# RackEth.net
KiCad netlist of a schematic drawn in EasyEDA Pro
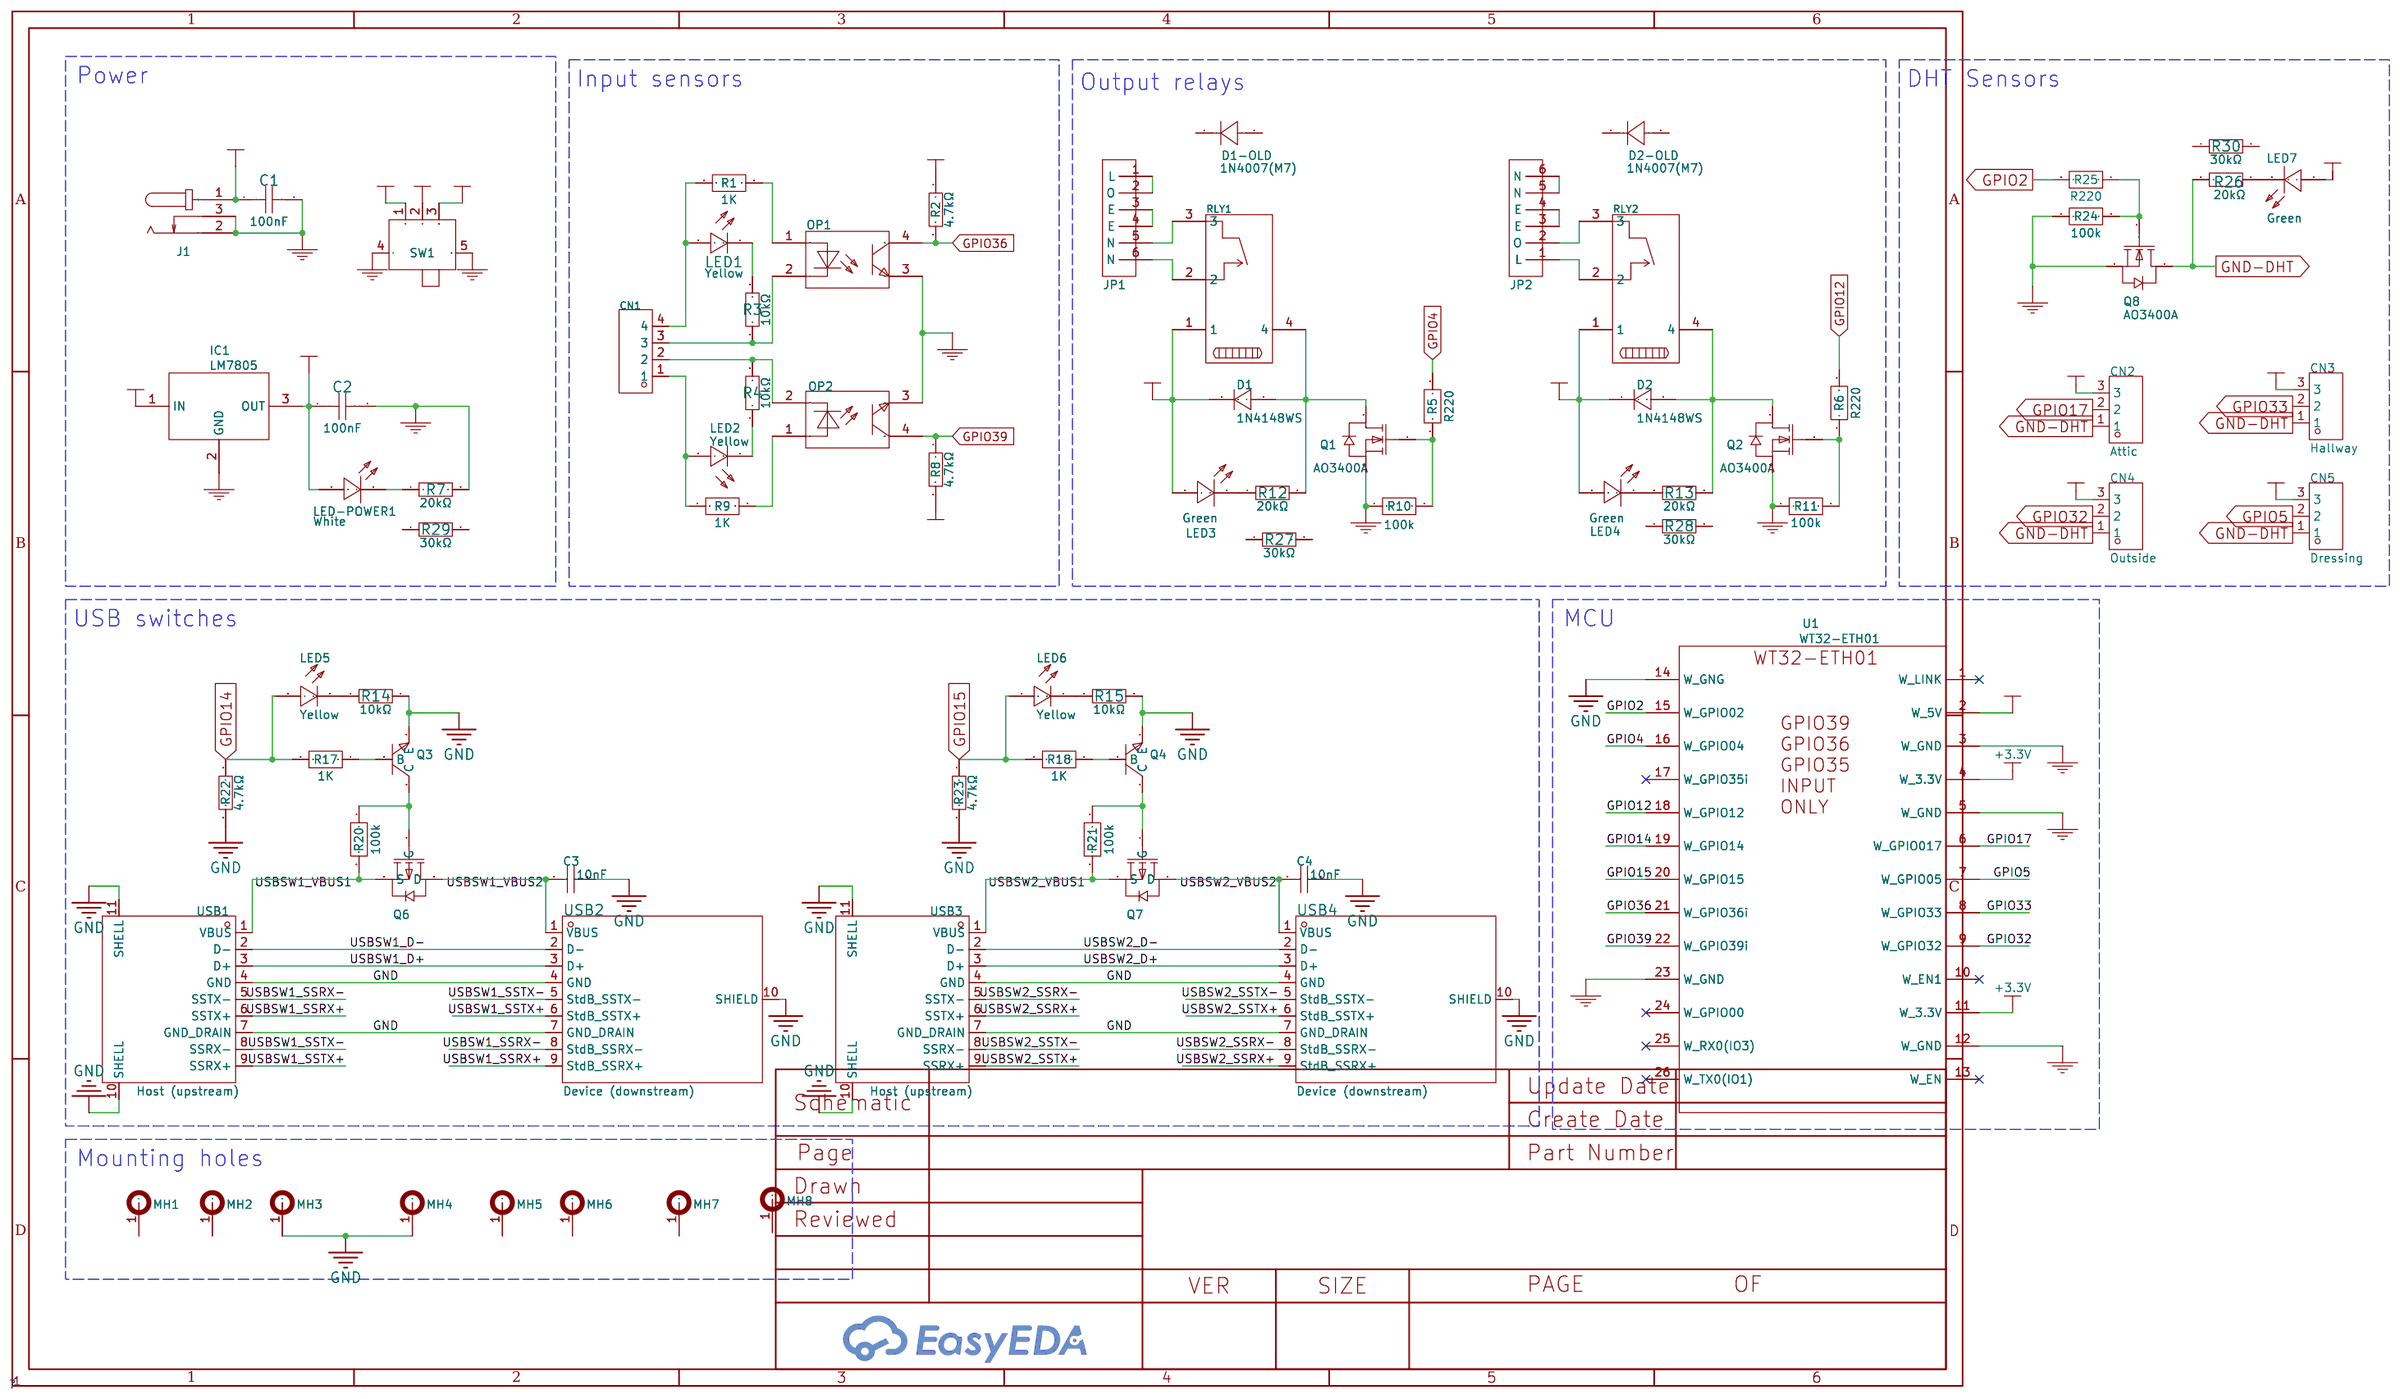
[diagram p0: schematic sheet]

(export (version "E")
  (design (tool "Eeschema 10.0.6"))
  (components
    (comp (ref "C1")
      (value "100nF")
      (footprint "easyedapro:C0603")
      (fields
        (field (name "Manufacturer Part") "CC0603KRX7R9BB104")
        (field (name "Manufacturer") "YAGEO(国巨)")
      )
      (libsource (lib "easyedapro") (part "CC0603KRX7R9BB104"))
    )
    (comp (ref "C2")
      (value "100nF")
      (footprint "easyedapro:C0603")
      (fields
        (field (name "Manufacturer Part") "CC0603KRX7R9BB104")
        (field (name "Manufacturer") "YAGEO(国巨)")
      )
      (libsource (lib "easyedapro") (part "CC0603KRX7R9BB104"))
    )
    (comp (ref "C3")
      (value "10nF")
      (footprint "easyedapro:C0402")
      (fields
        (field (name "Manufacturer Part") "CL05B103KB5NNNC")
        (field (name "Manufacturer") "SAMSUNG(三星)")
      )
      (libsource (lib "easyedapro") (part "CL05B103KB5NNNC"))
    )
    (comp (ref "C4")
      (value "10nF")
      (footprint "easyedapro:C0402")
      (fields
        (field (name "Manufacturer Part") "CL05B103KB5NNNC")
        (field (name "Manufacturer") "SAMSUNG(三星)")
      )
      (libsource (lib "easyedapro") (part "CL05B103KB5NNNC"))
    )
    (comp (ref "CN1")
      (value "WJ127-5.0-4P")
      (footprint "easyedapro:CONN-TH_4P-P5.00_WJ127-5.0-4P")
      (fields (field (name "Manufacturer") "KANGNEX(康奈克斯电气)"))
      (libsource (lib "easyedapro") (part "WJ127-5.0-4P"))
    )
    (comp (ref "CN2")
      (value "Attic")
      (footprint "easyedapro:CONN-TH_3P-P2.50_HCTL_XH-3A-L")
      (fields (field (name "Manufacturer Part") "XH2.54-3A"))
      (libsource (lib "easyedapro") (part "XH2.54-3A"))
    )
    (comp (ref "CN3")
      (value "Hallway")
      (footprint "easyedapro:CONN-TH_3P-P2.50_HCTL_XH-3A-L")
      (fields (field (name "Manufacturer Part") "XH2.54-3A"))
      (libsource (lib "easyedapro") (part "XH2.54-3A"))
    )
    (comp (ref "CN4")
      (value "Outside")
      (footprint "easyedapro:CONN-TH_3P-P2.50_HCTL_XH-3A-L")
      (fields (field (name "Manufacturer Part") "XH2.54-3A"))
      (libsource (lib "easyedapro") (part "XH2.54-3A"))
    )
    (comp (ref "CN5")
      (value "Dressing")
      (footprint "easyedapro:CONN-TH_3P-P2.50_HCTL_XH-3A-L")
      (fields (field (name "Manufacturer Part") "XH2.54-3A"))
      (libsource (lib "easyedapro") (part "XH2.54-3A"))
    )
    (comp (ref "D1")
      (value "1N4148WS")
      (footprint "easyedapro:SOD-323_L1.8-W1.3-LS2.5-RD")
      (fields (field (name "Manufacturer") "CJ(江苏长电/长晶)"))
      (libsource (lib "easyedapro") (part "1N4148WS T4"))
    )
    (comp (ref "D1-OLD")
      (value "1N4007(M7)")
      (footprint "easyedapro:SMA_L4.3-W2.7-LS5.1-RD")
      (fields (field (name "Manufacturer") "UMW(友台半导体)"))
      (libsource (lib "easyedapro") (part "1N4007(M7)"))
    )
    (comp (ref "D2")
      (value "1N4148WS")
      (footprint "easyedapro:SOD-323_L1.8-W1.3-LS2.5-RD")
      (fields (field (name "Manufacturer") "CJ(江苏长电/长晶)"))
      (libsource (lib "easyedapro") (part "1N4148WS T4"))
    )
    (comp (ref "D2-OLD")
      (value "1N4007(M7)")
      (footprint "easyedapro:SMA_L4.3-W2.7-LS5.1-RD")
      (fields (field (name "Manufacturer") "UMW(友台半导体)"))
      (libsource (lib "easyedapro") (part "1N4007(M7)"))
    )
    (comp (ref "IC1")
      (value "LM7805")
      (footprint "easyedapro:LM7805")
      (libsource (lib "easyedapro") (part "LM7805"))
    )
    (comp (ref "J1")
      (value "DC005-2.1x5.5mm")
      (footprint "easyedapro:DC-IN-TH_POWER-JACK")
      (fields (field (name "Manufacturer Part") "POWER-JACK") (field (name "Manufacturer") "索峰"))
      (libsource (lib "easyedapro") (part "DC005-2.1x5.5mm"))
    )
    (comp (ref "JP1") (value "JP1") (libsource (lib "easyedapro") (part "Terminal?")))
    (comp (ref "JP2") (value "JP2") (libsource (lib "easyedapro") (part "Terminal?")))
    (comp (ref "LED-POWER1")
      (value "White")
      (footprint "easyedapro:LED0603-R-RD_WHITE")
      (fields (field (name "Manufacturer Part") "KT-0603W") (field (name "Manufacturer") "KENTO"))
      (libsource (lib "easyedapro") (part "0603White light_C2290"))
    )
    (comp (ref "LED1")
      (value "Yellow")
      (footprint "easyedapro:LED0603-RD-YELLOW")
      (fields
        (field (name "Manufacturer Part") "19-213/Y2C-CQ2R2L/3T(CY)")
        (field (name "Manufacturer") "EVERLIGHT(亿光)")
      )
      (libsource (lib "easyedapro") (part "19-213/Y2C-CQ2R2L/3T(CY)"))
    )
    (comp (ref "LED2")
      (value "Yellow")
      (footprint "easyedapro:LED0603-RD-YELLOW")
      (fields
        (field (name "Manufacturer Part") "19-213/Y2C-CQ2R2L/3T(CY)")
        (field (name "Manufacturer") "EVERLIGHT(亿光)")
      )
      (libsource (lib "easyedapro") (part "19-213/Y2C-CQ2R2L/3T(CY)"))
    )
    (comp (ref "LED3")
      (value "Green")
      (footprint "easyedapro:LED0805-RD_GREEN")
      (fields (field (name "Manufacturer Part") "0805G (Green)") (field (name "Manufacturer") "KENTO"))
      (libsource (lib "easyedapro") (part "0805G (Green)"))
    )
    (comp (ref "LED4")
      (value "Green")
      (footprint "easyedapro:LED0805-RD_GREEN")
      (fields (field (name "Manufacturer Part") "0805G (Green)") (field (name "Manufacturer") "KENTO"))
      (libsource (lib "easyedapro") (part "0805G (Green)"))
    )
    (comp (ref "LED5")
      (value "Yellow")
      (footprint "easyedapro:LED0603-RD-YELLOW")
      (fields
        (field (name "Manufacturer Part") "19-213/Y2C-CQ2R2L/3T(CY)")
        (field (name "Manufacturer") "EVERLIGHT(亿光)")
      )
      (libsource (lib "easyedapro") (part "19-213/Y2C-CQ2R2L/3T(CY)"))
    )
    (comp (ref "LED6")
      (value "Yellow")
      (footprint "easyedapro:LED0603-RD-YELLOW")
      (fields
        (field (name "Manufacturer Part") "19-213/Y2C-CQ2R2L/3T(CY)")
        (field (name "Manufacturer") "EVERLIGHT(亿光)")
      )
      (libsource (lib "easyedapro") (part "19-213/Y2C-CQ2R2L/3T(CY)"))
    )
    (comp (ref "LED7")
      (value "Green")
      (footprint "easyedapro:LED0805-RD_GREEN")
      (fields (field (name "Manufacturer Part") "0805G (Green)") (field (name "Manufacturer") "KENTO"))
      (libsource (lib "easyedapro") (part "0805G (Green)"))
    )
    (comp (ref "MH1")
      (value "~")
      (footprint "easyedapro:MH_7.5x4mm")
      (libsource (lib "easyedapro") (part "MH_7.5x4mm"))
    )
    (comp (ref "MH2")
      (value "~")
      (footprint "easyedapro:MH_7.5x4mm")
      (libsource (lib "easyedapro") (part "MH_7.5x4mm"))
    )
    (comp (ref "MH3")
      (value "~")
      (footprint "easyedapro:MH_7.5x4mm")
      (libsource (lib "easyedapro") (part "MH_7.5x4mm"))
    )
    (comp (ref "MH4")
      (value "~")
      (footprint "easyedapro:MH_7.5x4mm")
      (libsource (lib "easyedapro") (part "MH_7.5x4mm"))
    )
    (comp (ref "MH5")
      (value "~")
      (footprint "easyedapro:MH_6x3.2mm")
      (libsource (lib "easyedapro") (part "MH_6x3.2mm"))
    )
    (comp (ref "MH6")
      (value "~")
      (footprint "easyedapro:MH_6x3.2mm")
      (libsource (lib "easyedapro") (part "MH_6x3.2mm"))
    )
    (comp (ref "MH7")
      (value "~")
      (footprint "easyedapro:MH_6x3.2mm")
      (libsource (lib "easyedapro") (part "MH_6x3.2mm"))
    )
    (comp (ref "MH8")
      (value "~")
      (footprint "easyedapro:MH_6x3.2mm")
      (libsource (lib "easyedapro") (part "MH_6x3.2mm"))
    )
    (comp (ref "OP1")
      (value "EL817S1(C)(TU)-F")
      (footprint "easyedapro:OPTO-SMD-4_L4.6-W6.5-P2.54-LS10.3-TL")
      (fields (field (name "Manufacturer") "EVERLIGHT(亿光)"))
      (libsource (lib "easyedapro") (part "EL817S1(C)(TU)-F"))
    )
    (comp (ref "OP2")
      (value "EL817S1(C)(TU)-F")
      (footprint "easyedapro:OPTO-SMD-4_L4.6-W6.5-P2.54-LS10.3-TL")
      (fields (field (name "Manufacturer") "EVERLIGHT(亿光)"))
      (libsource (lib "easyedapro") (part "EL817S1(C)(TU)-F"))
    )
    (comp (ref "Q1")
      (value "AO3400A")
      (footprint "easyedapro:SOT-23-3_L2.9-W1.6-P1.90-LS2.8-BR")
      (fields (field (name "Manufacturer") "AOS"))
      (libsource (lib "easyedapro") (part "AO3400A"))
    )
    (comp (ref "Q2")
      (value "AO3400A")
      (footprint "easyedapro:SOT-23-3_L2.9-W1.6-P1.90-LS2.8-BR")
      (fields (field (name "Manufacturer") "AOS"))
      (libsource (lib "easyedapro") (part "AO3400A"))
    )
    (comp (ref "Q3")
      (value "MMBT3904(RANGE:100-300)")
      (footprint "easyedapro:SOT-23-3_L2.9-W1.3-P1.90-LS2.4-BR")
      (fields (field (name "Manufacturer") "CJ(江苏长电/长晶)"))
      (libsource (lib "easyedapro") (part "MMBT3904"))
    )
    (comp (ref "Q4")
      (value "MMBT3904(RANGE:100-300)")
      (footprint "easyedapro:SOT-23-3_L2.9-W1.3-P1.90-LS2.4-BR")
      (fields (field (name "Manufacturer") "CJ(江苏长电/长晶)"))
      (libsource (lib "easyedapro") (part "MMBT3904"))
    )
    (comp (ref "Q6")
      (value "AO3401A")
      (footprint "easyedapro:SOT-23_L2.9-W1.3-P1.90-LS2.4-BR")
      (fields (field (name "Manufacturer") "AOS"))
      (libsource (lib "easyedapro") (part "AO3401A"))
    )
    (comp (ref "Q7")
      (value "AO3401A")
      (footprint "easyedapro:SOT-23_L2.9-W1.3-P1.90-LS2.4-BR")
      (fields (field (name "Manufacturer") "AOS"))
      (libsource (lib "easyedapro") (part "AO3401A"))
    )
    (comp (ref "Q8")
      (value "AO3400A")
      (footprint "easyedapro:SOT-23-3_L2.9-W1.6-P1.90-LS2.8-BR")
      (fields (field (name "Manufacturer") "AOS"))
      (libsource (lib "easyedapro") (part "AO3400A"))
    )
    (comp (ref "R1")
      (value "1K")
      (footprint "easyedapro:R0603")
      (fields
        (field (name "Manufacturer Part") "0603WAF1001T5E")
        (field (name "Manufacturer") "UNI-ROYAL(厚声)")
      )
      (libsource (lib "easyedapro") (part "1K"))
    )
    (comp (ref "R2")
      (value "4.7kΩ")
      (footprint "easyedapro:R0603")
      (fields
        (field (name "Manufacturer Part") "0603WAF4701T5E")
        (field (name "Manufacturer") "UNI-ROYAL(厚声)")
      )
      (libsource (lib "easyedapro") (part "0603WAF4701T5E"))
    )
    (comp (ref "R3")
      (value "10kΩ")
      (footprint "easyedapro:R0603")
      (fields
        (field (name "Manufacturer Part") "0603WAF1002T5E")
        (field (name "Manufacturer") "UNI-ROYAL(厚声)")
      )
      (libsource (lib "easyedapro") (part "0603WAF1002T5E"))
    )
    (comp (ref "R4")
      (value "10kΩ")
      (footprint "easyedapro:R0603")
      (fields
        (field (name "Manufacturer Part") "0603WAF1002T5E")
        (field (name "Manufacturer") "UNI-ROYAL(厚声)")
      )
      (libsource (lib "easyedapro") (part "0603WAF1002T5E"))
    )
    (comp (ref "R5")
      (value "R220")
      (footprint "easyedapro:R0603")
      (fields
        (field (name "Manufacturer Part") "0603WAF2200T5E")
        (field (name "Manufacturer") "UNI-ROYAL(厚声)")
      )
      (libsource (lib "easyedapro") (part "R220"))
    )
    (comp (ref "R6")
      (value "R220")
      (footprint "easyedapro:R0603")
      (fields
        (field (name "Manufacturer Part") "0603WAF2200T5E")
        (field (name "Manufacturer") "UNI-ROYAL(厚声)")
      )
      (libsource (lib "easyedapro") (part "R220"))
    )
    (comp (ref "R7")
      (value "20kΩ")
      (footprint "easyedapro:R0603")
      (fields
        (field (name "Manufacturer Part") "0603WAF2002T5E")
        (field (name "Manufacturer") "UNI-ROYAL(厚声)")
      )
      (libsource (lib "easyedapro") (part "0603WAF2002T5E"))
    )
    (comp (ref "R8")
      (value "4.7kΩ")
      (footprint "easyedapro:R0603")
      (fields
        (field (name "Manufacturer Part") "0603WAF4701T5E")
        (field (name "Manufacturer") "UNI-ROYAL(厚声)")
      )
      (libsource (lib "easyedapro") (part "0603WAF4701T5E"))
    )
    (comp (ref "R9")
      (value "1K")
      (footprint "easyedapro:R0603")
      (fields
        (field (name "Manufacturer Part") "0603WAF1001T5E")
        (field (name "Manufacturer") "UNI-ROYAL(厚声)")
      )
      (libsource (lib "easyedapro") (part "1K"))
    )
    (comp (ref "R10")
      (value "100k")
      (footprint "easyedapro:R0603")
      (fields
        (field (name "Manufacturer Part") "0603WAF1003T5E")
        (field (name "Manufacturer") "UNI-ROYAL(厚声)")
      )
      (libsource (lib "easyedapro") (part "100k"))
    )
    (comp (ref "R11")
      (value "100k")
      (footprint "easyedapro:R0603")
      (fields
        (field (name "Manufacturer Part") "0603WAF1003T5E")
        (field (name "Manufacturer") "UNI-ROYAL(厚声)")
      )
      (libsource (lib "easyedapro") (part "100k"))
    )
    (comp (ref "R12")
      (value "20kΩ")
      (footprint "easyedapro:R0603")
      (fields
        (field (name "Manufacturer Part") "0603WAF2002T5E")
        (field (name "Manufacturer") "UNI-ROYAL(厚声)")
      )
      (libsource (lib "easyedapro") (part "0603WAF2002T5E"))
    )
    (comp (ref "R13")
      (value "20kΩ")
      (footprint "easyedapro:R0603")
      (fields
        (field (name "Manufacturer Part") "0603WAF2002T5E")
        (field (name "Manufacturer") "UNI-ROYAL(厚声)")
      )
      (libsource (lib "easyedapro") (part "0603WAF2002T5E"))
    )
    (comp (ref "R14")
      (value "10kΩ")
      (footprint "easyedapro:R0603")
      (fields
        (field (name "Manufacturer Part") "0603WAF1002T5E")
        (field (name "Manufacturer") "UNI-ROYAL(厚声)")
      )
      (libsource (lib "easyedapro") (part "0603WAF1002T5E"))
    )
    (comp (ref "R15")
      (value "10kΩ")
      (footprint "easyedapro:R0603")
      (fields
        (field (name "Manufacturer Part") "0603WAF1002T5E")
        (field (name "Manufacturer") "UNI-ROYAL(厚声)")
      )
      (libsource (lib "easyedapro") (part "0603WAF1002T5E"))
    )
    (comp (ref "R17")
      (value "1K")
      (footprint "easyedapro:R0603")
      (fields
        (field (name "Manufacturer Part") "0603WAF1001T5E")
        (field (name "Manufacturer") "UNI-ROYAL(厚声)")
      )
      (libsource (lib "easyedapro") (part "1K"))
    )
    (comp (ref "R18")
      (value "1K")
      (footprint "easyedapro:R0603")
      (fields
        (field (name "Manufacturer Part") "0603WAF1001T5E")
        (field (name "Manufacturer") "UNI-ROYAL(厚声)")
      )
      (libsource (lib "easyedapro") (part "1K"))
    )
    (comp (ref "R20")
      (value "100k")
      (footprint "easyedapro:R0603")
      (fields
        (field (name "Manufacturer Part") "0603WAF1003T5E")
        (field (name "Manufacturer") "UNI-ROYAL(厚声)")
      )
      (libsource (lib "easyedapro") (part "100k"))
    )
    (comp (ref "R21")
      (value "100k")
      (footprint "easyedapro:R0603")
      (fields
        (field (name "Manufacturer Part") "0603WAF1003T5E")
        (field (name "Manufacturer") "UNI-ROYAL(厚声)")
      )
      (libsource (lib "easyedapro") (part "100k"))
    )
    (comp (ref "R22")
      (value "4.7kΩ")
      (footprint "easyedapro:R0603")
      (fields
        (field (name "Manufacturer Part") "0603WAF4701T5E")
        (field (name "Manufacturer") "UNI-ROYAL(厚声)")
      )
      (libsource (lib "easyedapro") (part "0603WAF4701T5E"))
    )
    (comp (ref "R23")
      (value "4.7kΩ")
      (footprint "easyedapro:R0603")
      (fields
        (field (name "Manufacturer Part") "0603WAF4701T5E")
        (field (name "Manufacturer") "UNI-ROYAL(厚声)")
      )
      (libsource (lib "easyedapro") (part "0603WAF4701T5E"))
    )
    (comp (ref "R24")
      (value "100k")
      (footprint "easyedapro:R0603")
      (fields
        (field (name "Manufacturer Part") "0603WAF1003T5E")
        (field (name "Manufacturer") "UNI-ROYAL(厚声)")
      )
      (libsource (lib "easyedapro") (part "100k"))
    )
    (comp (ref "R25")
      (value "R220")
      (footprint "easyedapro:R0603")
      (fields
        (field (name "Manufacturer Part") "0603WAF2200T5E")
        (field (name "Manufacturer") "UNI-ROYAL(厚声)")
      )
      (libsource (lib "easyedapro") (part "R220"))
    )
    (comp (ref "R26")
      (value "20kΩ")
      (footprint "easyedapro:R0603")
      (fields
        (field (name "Manufacturer Part") "0603WAF2002T5E")
        (field (name "Manufacturer") "UNI-ROYAL(厚声)")
      )
      (libsource (lib "easyedapro") (part "0603WAF2002T5E"))
    )
    (comp (ref "R27")
      (value "30kΩ")
      (footprint "easyedapro:R0603")
      (fields
        (field (name "Manufacturer Part") "0603WAF3002T5E")
        (field (name "Manufacturer") "UNI-ROYAL(厚声)")
      )
      (libsource (lib "easyedapro") (part "0603WAF3002T5E"))
    )
    (comp (ref "R28")
      (value "30kΩ")
      (footprint "easyedapro:R0603")
      (fields
        (field (name "Manufacturer Part") "0603WAF3002T5E")
        (field (name "Manufacturer") "UNI-ROYAL(厚声)")
      )
      (libsource (lib "easyedapro") (part "0603WAF3002T5E"))
    )
    (comp (ref "R29")
      (value "30kΩ")
      (footprint "easyedapro:R0603")
      (fields
        (field (name "Manufacturer Part") "0603WAF3002T5E")
        (field (name "Manufacturer") "UNI-ROYAL(厚声)")
      )
      (libsource (lib "easyedapro") (part "0603WAF3002T5E"))
    )
    (comp (ref "R30")
      (value "30kΩ")
      (footprint "easyedapro:R0603")
      (fields
        (field (name "Manufacturer Part") "0603WAF3002T5E")
        (field (name "Manufacturer") "UNI-ROYAL(厚声)")
      )
      (libsource (lib "easyedapro") (part "0603WAF3002T5E"))
    )
    (comp (ref "RLY1")
      (value "G5NB-1A-E-DC5V")
      (footprint "easyedapro:RELAY-TH_G5NB-1A-E-DCXX")
      (fields (field (name "Manufacturer") "OMRON(欧姆龙)"))
      (libsource (lib "easyedapro") (part "G5NB-1A-E-DC5V"))
    )
    (comp (ref "RLY2")
      (value "G5NB-1A-E-DC5V")
      (footprint "easyedapro:RELAY-TH_G5NB-1A-E-DCXX")
      (fields (field (name "Manufacturer") "OMRON(欧姆龙)"))
      (libsource (lib "easyedapro") (part "G5NB-1A-E-DC5V"))
    )
    (comp (ref "SW1")
      (value "SS12D07VG3 087")
      (footprint "easyedapro:SW-TH_SS12D07VG4")
      (fields (field (name "Manufacturer") "SHOU HAN(首韩)"))
      (libsource (lib "easyedapro") (part "SS12D07VG3 087"))
    )
    (comp (ref "U1")
      (value "WT32-ETH01")
      (footprint "easyedapro:WT32-ETH01-M")
      (fields (field (name "Manufacturer") "Wireless-Tag"))
      (libsource (lib "easyedapro") (part "WT32-ETH01"))
    )
    (comp (ref "USB1")
      (value "Host (upstream)")
      (footprint "easyedapro:USB3.0-TH_U235-09XN-2XC2-002")
      (fields
        (field (name "Manufacturer Part") "U235-091N-2UC2-002")
        (field (name "Manufacturer") "XKB Connection(中国星坤)")
      )
      (libsource (lib "easyedapro") (part "U235-091N-2UC2-002"))
    )
    (comp (ref "USB2")
      (value "Device (downstream)")
      (footprint "easyedapro:USB3.0-A-SMD_916-862A205EY10200")
      (fields (field (name "Manufacturer Part") "916-862A205EY10200") (field (name "Manufacturer") "精拓金"))
      (libsource (lib "easyedapro") (part "916-862A205EY10200"))
    )
    (comp (ref "USB3")
      (value "Host (upstream)")
      (footprint "easyedapro:USB3.0-TH_U235-09XN-2XC2-002")
      (fields
        (field (name "Manufacturer Part") "U235-091N-2UC2-002")
        (field (name "Manufacturer") "XKB Connection(中国星坤)")
      )
      (libsource (lib "easyedapro") (part "U235-091N-2UC2-002"))
    )
    (comp (ref "USB4")
      (value "Device (downstream)")
      (footprint "easyedapro:USB3.0-A-SMD_916-862A205EY10200")
      (fields (field (name "Manufacturer Part") "916-862A205EY10200") (field (name "Manufacturer") "精拓金"))
      (libsource (lib "easyedapro") (part "916-862A205EY10200"))
    )
  )
  (nets
    (net (code "1") (name "+3.3V") (class "Default")
      (node (ref "CN2") (pin "3") (pinfunction "3_3") (pintype "unspecified"))
      (node (ref "CN3") (pin "3") (pinfunction "3_3") (pintype "unspecified"))
      (node (ref "CN4") (pin "3") (pinfunction "3_3") (pintype "unspecified"))
      (node (ref "CN5") (pin "3") (pinfunction "3_3") (pintype "unspecified"))
      (node (ref "LED7") (pin "2") (pinfunction "A_2") (pintype "unspecified"))
      (node (ref "R2") (pin "1") (pinfunction "1_1") (pintype "input"))
      (node (ref "R8") (pin "2") (pinfunction "2_2") (pintype "input"))
      (node (ref "U1") (pin "11") (pinfunction "W_3.3V_11") (pintype "unspecified"))
      (node (ref "U1") (pin "4") (pinfunction "W_3.3V_4") (pintype "unspecified"))
    )
    (net (code "2") (name "+5V") (class "Default")
      (node (ref "C2") (pin "1") (pinfunction "1_1") (pintype "input"))
      (node (ref "D1") (pin "1") (pinfunction "K_1") (pintype "unspecified"))
      (node (ref "D2") (pin "1") (pinfunction "K_1") (pintype "unspecified"))
      (node (ref "IC1") (pin "3") (pinfunction "OUT_3") (pintype "unspecified"))
      (node (ref "LED-POWER1") (pin "1") (pinfunction "A_1") (pintype "unspecified"))
      (node (ref "LED3") (pin "2") (pinfunction "A_2") (pintype "unspecified"))
      (node (ref "LED4") (pin "2") (pinfunction "A_2") (pintype "unspecified"))
      (node (ref "RLY1") (pin "1") (pinfunction "1_1") (pintype "input"))
      (node (ref "RLY2") (pin "1") (pinfunction "1_1") (pintype "input"))
      (node (ref "SW1") (pin "1") (pinfunction "1_1") (pintype "unspecified"))
      (node (ref "U1") (pin "2") (pinfunction "W_5V_2") (pintype "unspecified"))
    )
    (net (code "3") (name "/USBSW1_D+") (class "Default")
      (node (ref "USB1") (pin "3") (pinfunction "D+_3") (pintype "unspecified"))
      (node (ref "USB2") (pin "3") (pinfunction "D+_3") (pintype "input"))
    )
    (net (code "4") (name "/USBSW1_D-") (class "Default")
      (node (ref "USB1") (pin "2") (pinfunction "D-_2") (pintype "unspecified"))
      (node (ref "USB2") (pin "2") (pinfunction "D-_2") (pintype "input"))
    )
    (net (code "5") (name "/USBSW1_SSRX+") (class "Default")
      (node (ref "USB1") (pin "6") (pinfunction "SSTX+_6") (pintype "unspecified"))
      (node (ref "USB2") (pin "9") (pinfunction "StdB_SSRX+_9") (pintype "input"))
    )
    (net (code "6") (name "/USBSW1_SSRX-") (class "Default")
      (node (ref "USB1") (pin "5") (pinfunction "SSTX-_5") (pintype "unspecified"))
      (node (ref "USB2") (pin "8") (pinfunction "StdB_SSRX-_8") (pintype "input"))
    )
    (net (code "7") (name "/USBSW1_SSTX+") (class "Default")
      (node (ref "USB1") (pin "9") (pinfunction "SSRX+_9") (pintype "unspecified"))
      (node (ref "USB2") (pin "6") (pinfunction "StdB_SSTX+_6") (pintype "input"))
    )
    (net (code "8") (name "/USBSW1_SSTX-") (class "Default")
      (node (ref "USB1") (pin "8") (pinfunction "SSRX-_8") (pintype "unspecified"))
      (node (ref "USB2") (pin "5") (pinfunction "StdB_SSTX-_5") (pintype "input"))
    )
    (net (code "9") (name "/USBSW1_VBUS1") (class "Default")
      (node (ref "Q6") (pin "2") (pinfunction "S_2") (pintype "unspecified"))
      (node (ref "R20") (pin "2") (pinfunction "2_2") (pintype "unspecified"))
      (node (ref "USB1") (pin "1") (pinfunction "VBUS_1") (pintype "unspecified"))
    )
    (net (code "10") (name "/USBSW1_VBUS2") (class "Default")
      (node (ref "C3") (pin "2") (pinfunction "2_2") (pintype "input"))
      (node (ref "Q6") (pin "3") (pinfunction "D_3") (pintype "unspecified"))
      (node (ref "USB2") (pin "1") (pinfunction "VBUS_1") (pintype "input"))
    )
    (net (code "11") (name "/USBSW2_D+") (class "Default")
      (node (ref "USB3") (pin "3") (pinfunction "D+_3") (pintype "unspecified"))
      (node (ref "USB4") (pin "3") (pinfunction "D+_3") (pintype "input"))
    )
    (net (code "12") (name "/USBSW2_D-") (class "Default")
      (node (ref "USB3") (pin "2") (pinfunction "D-_2") (pintype "unspecified"))
      (node (ref "USB4") (pin "2") (pinfunction "D-_2") (pintype "input"))
    )
    (net (code "13") (name "/USBSW2_SSRX+") (class "Default")
      (node (ref "USB3") (pin "6") (pinfunction "SSTX+_6") (pintype "unspecified"))
      (node (ref "USB4") (pin "9") (pinfunction "StdB_SSRX+_9") (pintype "input"))
    )
    (net (code "14") (name "/USBSW2_SSRX-") (class "Default")
      (node (ref "USB3") (pin "5") (pinfunction "SSTX-_5") (pintype "unspecified"))
      (node (ref "USB4") (pin "8") (pinfunction "StdB_SSRX-_8") (pintype "input"))
    )
    (net (code "15") (name "/USBSW2_SSTX+") (class "Default")
      (node (ref "USB3") (pin "9") (pinfunction "SSRX+_9") (pintype "unspecified"))
      (node (ref "USB4") (pin "6") (pinfunction "StdB_SSTX+_6") (pintype "input"))
    )
    (net (code "16") (name "/USBSW2_SSTX-") (class "Default")
      (node (ref "USB3") (pin "8") (pinfunction "SSRX-_8") (pintype "unspecified"))
      (node (ref "USB4") (pin "5") (pinfunction "StdB_SSTX-_5") (pintype "input"))
    )
    (net (code "17") (name "/USBSW2_VBUS1") (class "Default")
      (node (ref "Q7") (pin "2") (pinfunction "S_2") (pintype "unspecified"))
      (node (ref "R21") (pin "2") (pinfunction "2_2") (pintype "unspecified"))
      (node (ref "USB3") (pin "1") (pinfunction "VBUS_1") (pintype "unspecified"))
    )
    (net (code "18") (name "/USBSW2_VBUS2") (class "Default")
      (node (ref "C4") (pin "2") (pinfunction "2_2") (pintype "input"))
      (node (ref "Q7") (pin "3") (pinfunction "D_3") (pintype "unspecified"))
      (node (ref "USB4") (pin "1") (pinfunction "VBUS_1") (pintype "input"))
    )
    (net (code "19") (name "GND") (class "Default")
      (node (ref "C1") (pin "2") (pinfunction "2_2") (pintype "input"))
      (node (ref "C2") (pin "2") (pinfunction "2_2") (pintype "input"))
      (node (ref "C3") (pin "1") (pinfunction "1_1") (pintype "input"))
      (node (ref "C4") (pin "1") (pinfunction "1_1") (pintype "input"))
      (node (ref "IC1") (pin "2") (pinfunction "GND_2") (pintype "unspecified"))
      (node (ref "J1") (pin "2") (pinfunction "GND_2") (pintype "unspecified"))
      (node (ref "J1") (pin "3") (pinfunction "3_3") (pintype "unspecified"))
      (node (ref "MH3") (pin "1") (pinfunction "1_1") (pintype "input"))
      (node (ref "MH4") (pin "1") (pinfunction "1_1") (pintype "input"))
      (node (ref "OP1") (pin "3") (pinfunction "EM_3") (pintype "unspecified"))
      (node (ref "OP2") (pin "3") (pinfunction "EM_3") (pintype "unspecified"))
      (node (ref "Q1") (pin "2") (pinfunction "S_2") (pintype "unspecified"))
      (node (ref "Q2") (pin "2") (pinfunction "S_2") (pintype "unspecified"))
      (node (ref "Q3") (pin "2") (pinfunction "E_2") (pintype "unspecified"))
      (node (ref "Q4") (pin "2") (pinfunction "E_2") (pintype "unspecified"))
      (node (ref "Q8") (pin "2") (pinfunction "S_2") (pintype "unspecified"))
      (node (ref "R10") (pin "1") (pinfunction "1_1") (pintype "unspecified"))
      (node (ref "R11") (pin "1") (pinfunction "1_1") (pintype "unspecified"))
      (node (ref "R14") (pin "1") (pinfunction "1_1") (pintype "input"))
      (node (ref "R15") (pin "1") (pinfunction "1_1") (pintype "input"))
      (node (ref "R22") (pin "2") (pinfunction "2_2") (pintype "input"))
      (node (ref "R23") (pin "2") (pinfunction "2_2") (pintype "input"))
      (node (ref "R24") (pin "1") (pinfunction "1_1") (pintype "unspecified"))
      (node (ref "R7") (pin "2") (pinfunction "2_2") (pintype "input"))
      (node (ref "SW1") (pin "4") (pinfunction "4_4") (pintype "unspecified"))
      (node (ref "SW1") (pin "5") (pinfunction "5_5") (pintype "unspecified"))
      (node (ref "U1") (pin "12") (pinfunction "W_GND_12") (pintype "unspecified"))
      (node (ref "U1") (pin "14") (pinfunction "W_GNG_14") (pintype "unspecified"))
      (node (ref "U1") (pin "23") (pinfunction "W_GND_23") (pintype "unspecified"))
      (node (ref "U1") (pin "3") (pinfunction "W_GND_3") (pintype "unspecified"))
      (node (ref "U1") (pin "5") (pinfunction "W_GND_5") (pintype "unspecified"))
      (node (ref "USB1") (pin "10") (pinfunction "SHELL_10") (pintype "unspecified"))
      (node (ref "USB1") (pin "11") (pinfunction "SHELL_11") (pintype "unspecified"))
      (node (ref "USB1") (pin "4") (pinfunction "GND_4") (pintype "unspecified"))
      (node (ref "USB1") (pin "7") (pinfunction "GND_DRAIN_7") (pintype "unspecified"))
      (node (ref "USB2") (pin "10") (pinfunction "SHIELD_10") (pintype "input"))
      (node (ref "USB2") (pin "4") (pinfunction "GND_4") (pintype "input"))
      (node (ref "USB2") (pin "7") (pinfunction "GND_DRAIN_7") (pintype "input"))
      (node (ref "USB3") (pin "10") (pinfunction "SHELL_10") (pintype "unspecified"))
      (node (ref "USB3") (pin "11") (pinfunction "SHELL_11") (pintype "unspecified"))
      (node (ref "USB3") (pin "4") (pinfunction "GND_4") (pintype "unspecified"))
      (node (ref "USB3") (pin "7") (pinfunction "GND_DRAIN_7") (pintype "unspecified"))
      (node (ref "USB4") (pin "10") (pinfunction "SHIELD_10") (pintype "input"))
      (node (ref "USB4") (pin "4") (pinfunction "GND_4") (pintype "input"))
      (node (ref "USB4") (pin "7") (pinfunction "GND_DRAIN_7") (pintype "input"))
    )
    (net (code "20") (name "GND-DHT") (class "Default")
      (node (ref "CN2") (pin "1") (pinfunction "1_1") (pintype "unspecified"))
      (node (ref "CN3") (pin "1") (pinfunction "1_1") (pintype "unspecified"))
      (node (ref "CN4") (pin "1") (pinfunction "1_1") (pintype "unspecified"))
      (node (ref "CN5") (pin "1") (pinfunction "1_1") (pintype "unspecified"))
      (node (ref "Q8") (pin "3") (pinfunction "D_3") (pintype "unspecified"))
      (node (ref "R26") (pin "2") (pinfunction "2_2") (pintype "input"))
    )
    (net (code "21") (name "GPIO2") (class "Default")
      (node (ref "R25") (pin "2") (pinfunction "2_2") (pintype "unspecified"))
      (node (ref "U1") (pin "15") (pinfunction "W_GPIO02_15") (pintype "unspecified"))
    )
    (net (code "22") (name "GPIO4") (class "Default")
      (node (ref "R5") (pin "2") (pinfunction "2_2") (pintype "unspecified"))
      (node (ref "U1") (pin "16") (pinfunction "W_GPIO04_16") (pintype "unspecified"))
    )
    (net (code "23") (name "GPIO5") (class "Default")
      (node (ref "CN5") (pin "2") (pinfunction "2_2") (pintype "unspecified"))
      (node (ref "U1") (pin "7") (pinfunction "W_GPIO05_7") (pintype "unspecified"))
    )
    (net (code "24") (name "GPIO12") (class "Default")
      (node (ref "R6") (pin "2") (pinfunction "2_2") (pintype "unspecified"))
      (node (ref "U1") (pin "18") (pinfunction "W_GPIO12_18") (pintype "unspecified"))
    )
    (net (code "25") (name "GPIO14") (class "Default")
      (node (ref "LED5") (pin "2") (pinfunction "A_2") (pintype "input"))
      (node (ref "R17") (pin "2") (pinfunction "2_2") (pintype "unspecified"))
      (node (ref "R22") (pin "1") (pinfunction "1_1") (pintype "input"))
      (node (ref "U1") (pin "19") (pinfunction "W_GPIO14_19") (pintype "unspecified"))
    )
    (net (code "26") (name "GPIO15") (class "Default")
      (node (ref "LED6") (pin "2") (pinfunction "A_2") (pintype "input"))
      (node (ref "R18") (pin "2") (pinfunction "2_2") (pintype "unspecified"))
      (node (ref "R23") (pin "1") (pinfunction "1_1") (pintype "input"))
      (node (ref "U1") (pin "20") (pinfunction "W_GPIO15_20") (pintype "unspecified"))
    )
    (net (code "27") (name "GPIO17") (class "Default")
      (node (ref "CN2") (pin "2") (pinfunction "2_2") (pintype "unspecified"))
      (node (ref "U1") (pin "6") (pinfunction "W_GPIO017_6") (pintype "unspecified"))
    )
    (net (code "28") (name "GPIO32") (class "Default")
      (node (ref "CN4") (pin "2") (pinfunction "2_2") (pintype "unspecified"))
      (node (ref "U1") (pin "9") (pinfunction "W_GPIO32_9") (pintype "unspecified"))
    )
    (net (code "29") (name "GPIO33") (class "Default")
      (node (ref "CN3") (pin "2") (pinfunction "2_2") (pintype "unspecified"))
      (node (ref "U1") (pin "8") (pinfunction "W_GPIO33_8") (pintype "unspecified"))
    )
    (net (code "30") (name "GPIO36") (class "Default")
      (node (ref "OP1") (pin "4") (pinfunction "COL_4") (pintype "unspecified"))
      (node (ref "R2") (pin "2") (pinfunction "2_2") (pintype "input"))
      (node (ref "U1") (pin "21") (pinfunction "W_GPIO36i_21") (pintype "unspecified"))
    )
    (net (code "31") (name "GPIO39") (class "Default")
      (node (ref "OP2") (pin "4") (pinfunction "COL_4") (pintype "unspecified"))
      (node (ref "R8") (pin "1") (pinfunction "1_1") (pintype "input"))
      (node (ref "U1") (pin "22") (pinfunction "W_GPIO39i_22") (pintype "unspecified"))
    )
    (net (code "32") (name "Net-(D1-A)") (class "Default")
      (node (ref "D1") (pin "2") (pinfunction "A_2") (pintype "unspecified"))
      (node (ref "Q1") (pin "3") (pinfunction "D_3") (pintype "unspecified"))
      (node (ref "R12") (pin "2") (pinfunction "2_2") (pintype "input"))
      (node (ref "RLY1") (pin "4") (pinfunction "4_4") (pintype "input"))
    )
    (net (code "33") (name "Net-(D2-A)") (class "Default")
      (node (ref "D2") (pin "2") (pinfunction "A_2") (pintype "unspecified"))
      (node (ref "Q2") (pin "3") (pinfunction "D_3") (pintype "unspecified"))
      (node (ref "R13") (pin "2") (pinfunction "2_2") (pintype "input"))
      (node (ref "RLY2") (pin "4") (pinfunction "4_4") (pintype "input"))
    )
    (net (code "34") (name "Net-(JP1-E-Pad3)") (class "Default")
      (node (ref "JP1") (pin "3") (pinfunction "E_3") (pintype "unspecified"))
      (node (ref "JP1") (pin "4") (pinfunction "E_4") (pintype "unspecified"))
    )
    (net (code "35") (name "Net-(JP1-L)") (class "Default")
      (node (ref "JP1") (pin "1") (pinfunction "L_1") (pintype "unspecified"))
      (node (ref "JP1") (pin "2") (pinfunction "O_2") (pintype "unspecified"))
    )
    (net (code "36") (name "Net-(JP1-N-Pad5)") (class "Default")
      (node (ref "JP1") (pin "5") (pinfunction "N_5") (pintype "unspecified"))
      (node (ref "RLY1") (pin "3") (pinfunction "3_3") (pintype "input"))
    )
    (net (code "37") (name "Net-(JP1-N-Pad6)") (class "Default")
      (node (ref "JP1") (pin "6") (pinfunction "N_6") (pintype "unspecified"))
      (node (ref "RLY1") (pin "2") (pinfunction "2_2") (pintype "input"))
    )
    (net (code "38") (name "Net-(JP2-E-Pad3)") (class "Default")
      (node (ref "JP2") (pin "3") (pinfunction "E_3") (pintype "unspecified"))
      (node (ref "JP2") (pin "4") (pinfunction "E_4") (pintype "unspecified"))
    )
    (net (code "39") (name "Net-(JP2-L)") (class "Default")
      (node (ref "JP2") (pin "1") (pinfunction "L_1") (pintype "unspecified"))
      (node (ref "RLY2") (pin "2") (pinfunction "2_2") (pintype "input"))
    )
    (net (code "40") (name "Net-(JP2-N-Pad5)") (class "Default")
      (node (ref "JP2") (pin "5") (pinfunction "N_5") (pintype "unspecified"))
      (node (ref "JP2") (pin "6") (pinfunction "N_6") (pintype "unspecified"))
    )
    (net (code "41") (name "Net-(JP2-O)") (class "Default")
      (node (ref "JP2") (pin "2") (pinfunction "O_2") (pintype "unspecified"))
      (node (ref "RLY2") (pin "3") (pinfunction "3_3") (pintype "input"))
    )
    (net (code "42") (name "Net-(LED-POWER1-K)") (class "Default")
      (node (ref "LED-POWER1") (pin "2") (pinfunction "K_2") (pintype "unspecified"))
      (node (ref "R7") (pin "1") (pinfunction "1_1") (pintype "input"))
    )
    (net (code "43") (name "Net-(LED1-A)") (class "Default")
      (node (ref "CN1") (pin "4") (pinfunction "4_4") (pintype "input"))
      (node (ref "LED1") (pin "2") (pinfunction "A_2") (pintype "input"))
      (node (ref "R1") (pin "2") (pinfunction "2_2") (pintype "unspecified"))
    )
    (net (code "44") (name "Net-(LED1-C)") (class "Default")
      (node (ref "LED1") (pin "1") (pinfunction "C_1") (pintype "input"))
      (node (ref "R3") (pin "2") (pinfunction "2_2") (pintype "input"))
    )
    (net (code "45") (name "Net-(LED2-A)") (class "Default")
      (node (ref "CN1") (pin "1") (pinfunction "1_1") (pintype "input"))
      (node (ref "LED2") (pin "2") (pinfunction "A_2") (pintype "input"))
      (node (ref "R9") (pin "1") (pinfunction "1_1") (pintype "unspecified"))
    )
    (net (code "46") (name "Net-(LED2-C)") (class "Default")
      (node (ref "LED2") (pin "1") (pinfunction "C_1") (pintype "input"))
      (node (ref "R4") (pin "1") (pinfunction "1_1") (pintype "input"))
    )
    (net (code "47") (name "Net-(LED3-K)") (class "Default")
      (node (ref "LED3") (pin "1") (pinfunction "K_1") (pintype "unspecified"))
      (node (ref "R12") (pin "1") (pinfunction "1_1") (pintype "input"))
    )
    (net (code "48") (name "Net-(LED4-K)") (class "Default")
      (node (ref "LED4") (pin "1") (pinfunction "K_1") (pintype "unspecified"))
      (node (ref "R13") (pin "1") (pinfunction "1_1") (pintype "input"))
    )
    (net (code "49") (name "Net-(LED5-C)") (class "Default")
      (node (ref "LED5") (pin "1") (pinfunction "C_1") (pintype "input"))
      (node (ref "R14") (pin "2") (pinfunction "2_2") (pintype "input"))
    )
    (net (code "50") (name "Net-(LED6-C)") (class "Default")
      (node (ref "LED6") (pin "1") (pinfunction "C_1") (pintype "input"))
      (node (ref "R15") (pin "2") (pinfunction "2_2") (pintype "input"))
    )
    (net (code "51") (name "Net-(LED7-K)") (class "Default")
      (node (ref "LED7") (pin "1") (pinfunction "K_1") (pintype "unspecified"))
      (node (ref "R26") (pin "1") (pinfunction "1_1") (pintype "input"))
    )
    (net (code "52") (name "Net-(OP1-AN)") (class "Default")
      (node (ref "OP1") (pin "1") (pinfunction "AN_1") (pintype "unspecified"))
      (node (ref "R1") (pin "1") (pinfunction "1_1") (pintype "unspecified"))
    )
    (net (code "53") (name "Net-(OP1-CAT)") (class "Default")
      (node (ref "CN1") (pin "3") (pinfunction "3_3") (pintype "input"))
      (node (ref "OP1") (pin "2") (pinfunction "CAT_2") (pintype "unspecified"))
      (node (ref "R3") (pin "1") (pinfunction "1_1") (pintype "input"))
    )
    (net (code "54") (name "Net-(OP2-AN)") (class "Default")
      (node (ref "OP2") (pin "1") (pinfunction "AN_1") (pintype "unspecified"))
      (node (ref "R9") (pin "2") (pinfunction "2_2") (pintype "unspecified"))
    )
    (net (code "55") (name "Net-(OP2-CAT)") (class "Default")
      (node (ref "CN1") (pin "2") (pinfunction "2_2") (pintype "input"))
      (node (ref "OP2") (pin "2") (pinfunction "CAT_2") (pintype "unspecified"))
      (node (ref "R4") (pin "2") (pinfunction "2_2") (pintype "input"))
    )
    (net (code "56") (name "Net-(Q1-G)") (class "Default")
      (node (ref "Q1") (pin "1") (pinfunction "G_1") (pintype "unspecified"))
      (node (ref "R10") (pin "2") (pinfunction "2_2") (pintype "unspecified"))
      (node (ref "R5") (pin "1") (pinfunction "1_1") (pintype "unspecified"))
    )
    (net (code "57") (name "Net-(Q2-G)") (class "Default")
      (node (ref "Q2") (pin "1") (pinfunction "G_1") (pintype "unspecified"))
      (node (ref "R11") (pin "2") (pinfunction "2_2") (pintype "unspecified"))
      (node (ref "R6") (pin "1") (pinfunction "1_1") (pintype "unspecified"))
    )
    (net (code "58") (name "Net-(Q3-B)") (class "Default")
      (node (ref "Q3") (pin "1") (pinfunction "B_1") (pintype "unspecified"))
      (node (ref "R17") (pin "1") (pinfunction "1_1") (pintype "unspecified"))
    )
    (net (code "59") (name "Net-(Q3-C)") (class "Default")
      (node (ref "Q3") (pin "3") (pinfunction "C_3") (pintype "unspecified"))
      (node (ref "Q6") (pin "1") (pinfunction "G_1") (pintype "unspecified"))
      (node (ref "R20") (pin "1") (pinfunction "1_1") (pintype "unspecified"))
    )
    (net (code "60") (name "Net-(Q4-B)") (class "Default")
      (node (ref "Q4") (pin "1") (pinfunction "B_1") (pintype "unspecified"))
      (node (ref "R18") (pin "1") (pinfunction "1_1") (pintype "unspecified"))
    )
    (net (code "61") (name "Net-(Q4-C)") (class "Default")
      (node (ref "Q4") (pin "3") (pinfunction "C_3") (pintype "unspecified"))
      (node (ref "Q7") (pin "1") (pinfunction "G_1") (pintype "unspecified"))
      (node (ref "R21") (pin "1") (pinfunction "1_1") (pintype "unspecified"))
    )
    (net (code "62") (name "Net-(Q8-G)") (class "Default")
      (node (ref "Q8") (pin "1") (pinfunction "G_1") (pintype "unspecified"))
      (node (ref "R24") (pin "2") (pinfunction "2_2") (pintype "unspecified"))
      (node (ref "R25") (pin "1") (pinfunction "1_1") (pintype "unspecified"))
    )
    (net (code "63") (name "VCC") (class "Default")
      (node (ref "IC1") (pin "1") (pinfunction "IN_1") (pintype "unspecified"))
      (node (ref "SW1") (pin "3") (pinfunction "3_3") (pintype "unspecified"))
    )
    (net (code "64") (name "VCC-IN") (class "Default")
      (node (ref "C1") (pin "1") (pinfunction "1_1") (pintype "input"))
      (node (ref "J1") (pin "1") (pinfunction "VCC_1") (pintype "unspecified"))
      (node (ref "SW1") (pin "2") (pinfunction "2_2") (pintype "unspecified"))
    )
    (net (code "65") (name "unconnected-(D1-OLD-A-Pad2)") (class "Default")
      (node (ref "D1-OLD") (pin "2") (pinfunction "A_2") (pintype "unspecified"))
    )
    (net (code "66") (name "unconnected-(D1-OLD-K-Pad1)") (class "Default")
      (node (ref "D1-OLD") (pin "1") (pinfunction "K_1") (pintype "unspecified"))
    )
    (net (code "67") (name "unconnected-(D2-OLD-A-Pad2)") (class "Default")
      (node (ref "D2-OLD") (pin "2") (pinfunction "A_2") (pintype "unspecified"))
    )
    (net (code "68") (name "unconnected-(D2-OLD-K-Pad1)") (class "Default")
      (node (ref "D2-OLD") (pin "1") (pinfunction "K_1") (pintype "unspecified"))
    )
    (net (code "69") (name "unconnected-(MH1-Pad1)") (class "Default")
      (node (ref "MH1") (pin "1") (pinfunction "1_1") (pintype "input"))
    )
    (net (code "70") (name "unconnected-(MH2-Pad1)") (class "Default")
      (node (ref "MH2") (pin "1") (pinfunction "1_1") (pintype "input"))
    )
    (net (code "71") (name "unconnected-(MH5-Pad1)") (class "Default")
      (node (ref "MH5") (pin "1") (pinfunction "1_1") (pintype "input"))
    )
    (net (code "72") (name "unconnected-(MH6-Pad1)") (class "Default")
      (node (ref "MH6") (pin "1") (pinfunction "1_1") (pintype "input"))
    )
    (net (code "73") (name "unconnected-(MH7-Pad1)") (class "Default")
      (node (ref "MH7") (pin "1") (pinfunction "1_1") (pintype "input"))
    )
    (net (code "74") (name "unconnected-(MH8-Pad1)") (class "Default")
      (node (ref "MH8") (pin "1") (pinfunction "1_1") (pintype "input"))
    )
    (net (code "75") (name "unconnected-(R27-Pad1)") (class "Default")
      (node (ref "R27") (pin "1") (pinfunction "1_1") (pintype "input"))
    )
    (net (code "76") (name "unconnected-(R27-Pad2)") (class "Default")
      (node (ref "R27") (pin "2") (pinfunction "2_2") (pintype "input"))
    )
    (net (code "77") (name "unconnected-(R28-Pad1)") (class "Default")
      (node (ref "R28") (pin "1") (pinfunction "1_1") (pintype "input"))
    )
    (net (code "78") (name "unconnected-(R28-Pad2)") (class "Default")
      (node (ref "R28") (pin "2") (pinfunction "2_2") (pintype "input"))
    )
    (net (code "79") (name "unconnected-(R29-Pad1)") (class "Default")
      (node (ref "R29") (pin "1") (pinfunction "1_1") (pintype "input"))
    )
    (net (code "80") (name "unconnected-(R29-Pad2)") (class "Default")
      (node (ref "R29") (pin "2") (pinfunction "2_2") (pintype "input"))
    )
    (net (code "81") (name "unconnected-(R30-Pad1)") (class "Default")
      (node (ref "R30") (pin "1") (pinfunction "1_1") (pintype "input"))
    )
    (net (code "82") (name "unconnected-(R30-Pad2)") (class "Default")
      (node (ref "R30") (pin "2") (pinfunction "2_2") (pintype "input"))
    )
    (net (code "83") (name "unconnected-(U1-W_EN-Pad13)") (class "Default")
      (node (ref "U1") (pin "13") (pinfunction "W_EN_13") (pintype "unspecified+no_connect"))
    )
    (net (code "84") (name "unconnected-(U1-W_EN1-Pad10)") (class "Default")
      (node (ref "U1") (pin "10") (pinfunction "W_EN1_10") (pintype "unspecified+no_connect"))
    )
    (net (code "85") (name "unconnected-(U1-W_GPIO00-Pad24)") (class "Default")
      (node (ref "U1") (pin "24") (pinfunction "W_GPIO00_24") (pintype "unspecified+no_connect"))
    )
    (net (code "86") (name "unconnected-(U1-W_GPIO35i-Pad17)") (class "Default")
      (node (ref "U1") (pin "17") (pinfunction "W_GPIO35i_17") (pintype "unspecified+no_connect"))
    )
    (net (code "87") (name "unconnected-(U1-W_LINK-Pad1)") (class "Default")
      (node (ref "U1") (pin "1") (pinfunction "W_LINK_1") (pintype "unspecified+no_connect"))
    )
    (net (code "88") (name "unconnected-(U1-W_RX0(IO3)-Pad25)") (class "Default")
      (node (ref "U1") (pin "25") (pinfunction "W_RX0(IO3)_25") (pintype "unspecified+no_connect"))
    )
    (net (code "89") (name "unconnected-(U1-W_TX0(IO1)-Pad26)") (class "Default")
      (node (ref "U1") (pin "26") (pinfunction "W_TX0(IO1)_26") (pintype "unspecified+no_connect"))
    )
  )
)
